# flip_flop_4LED.net
KiCad netlist of a schematic drawn in EAGLE
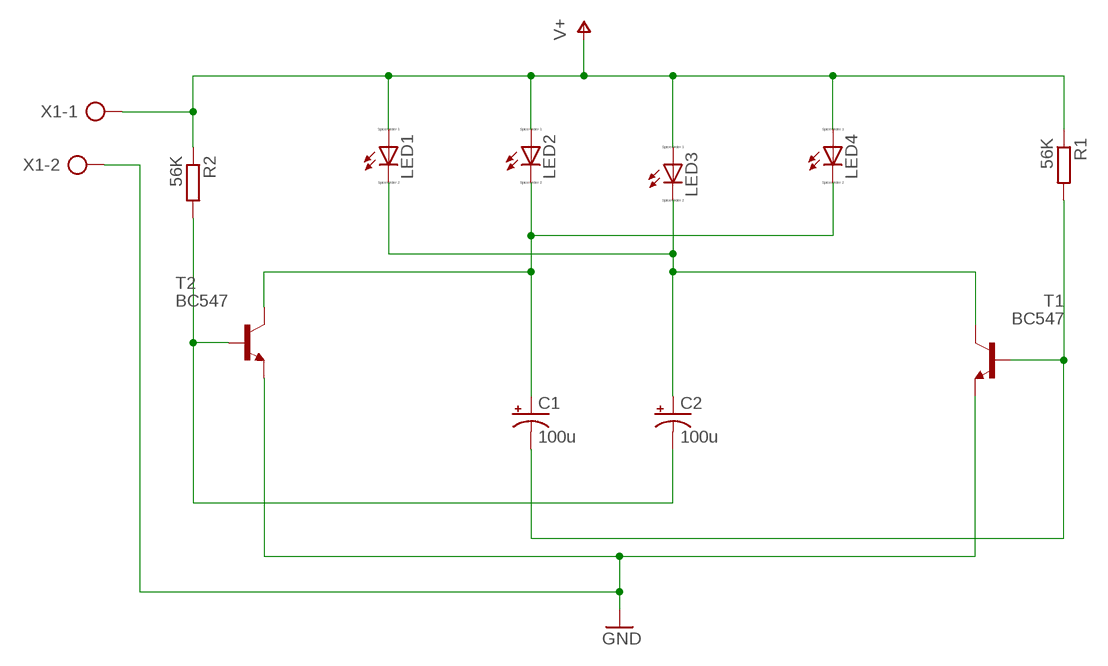
[diagram p0: schematic, sheet 1]

(export (version "E")
  (design (tool "Eeschema 10.0.6"))
  (components
    (comp (ref "C1")
      (value "100u")
      (footprint "eagle-import:E5-5")
      (libsource (lib "eagle-import") (part "CPOL-USE5-5"))
    )
    (comp (ref "C2")
      (value "100u")
      (footprint "eagle-import:E5-5")
      (libsource (lib "eagle-import") (part "CPOL-USE5-5"))
    )
    (comp (ref "LED1")
      (value "LED_ELD260")
      (footprint "eagle-import:LED_LD260")
      (libsource (lib "eagle-import") (part "LED_ELD260"))
    )
    (comp (ref "LED2")
      (value "LED_ELD260")
      (footprint "eagle-import:LED_LD260")
      (libsource (lib "eagle-import") (part "LED_ELD260"))
    )
    (comp (ref "LED3")
      (value "LED_ELD260")
      (footprint "eagle-import:LED_LD260")
      (libsource (lib "eagle-import") (part "LED_ELD260"))
    )
    (comp (ref "LED4")
      (value "LED_ELD260")
      (footprint "eagle-import:LED_LD260")
      (libsource (lib "eagle-import") (part "LED_ELD260"))
    )
    (comp (ref "R1")
      (value "56K")
      (footprint "eagle-import:0309_12")
      (libsource (lib "eagle-import") (part "R-EU_0309/12"))
    )
    (comp (ref "R2")
      (value "56K")
      (footprint "eagle-import:0309_12")
      (libsource (lib "eagle-import") (part "R-EU_0309/12"))
    )
    (comp (ref "T1")
      (value "BC547")
      (footprint "eagle-import:TO92")
      (libsource (lib "eagle-import") (part "BC547"))
    )
    (comp (ref "T2")
      (value "BC547")
      (footprint "eagle-import:TO92")
      (libsource (lib "eagle-import") (part "BC547"))
    )
    (comp (ref "X1")
      (value "AK500/2-H")
      (footprint "eagle-import:AK500_2-H")
      (libsource (lib "eagle-import") (part "AK500/2-H"))
    )
  )
  (nets
    (net (code "1") (name "GND") (class "Default")
      (node (ref "T1") (pin "1") (pinfunction "E_1") (pintype "passive"))
      (node (ref "T2") (pin "1") (pinfunction "E_1") (pintype "passive"))
      (node (ref "X1") (pin "2") (pinfunction "KL_2") (pintype "passive"))
    )
    (net (code "2") (name "Net-(LED1-C)") (class "Default")
      (node (ref "C2") (pin "+") (pinfunction "+_+") (pintype "passive"))
      (node (ref "LED1") (pin "K") (pinfunction "C_K") (pintype "passive"))
      (node (ref "LED3") (pin "K") (pinfunction "C_K") (pintype "passive"))
      (node (ref "T1") (pin "3") (pinfunction "C_3") (pintype "passive"))
    )
    (net (code "3") (name "Net-(LED2-C)") (class "Default")
      (node (ref "C1") (pin "+") (pinfunction "+_+") (pintype "passive"))
      (node (ref "LED2") (pin "K") (pinfunction "C_K") (pintype "passive"))
      (node (ref "LED4") (pin "K") (pinfunction "C_K") (pintype "passive"))
      (node (ref "T2") (pin "3") (pinfunction "C_3") (pintype "passive"))
    )
    (net (code "4") (name "Net-(T1-B)") (class "Default")
      (node (ref "C1") (pin "-") (pinfunction "-_-") (pintype "passive"))
      (node (ref "R1") (pin "2") (pinfunction "2_2") (pintype "passive"))
      (node (ref "T1") (pin "2") (pinfunction "B_2") (pintype "passive"))
    )
    (net (code "5") (name "Net-(T2-B)") (class "Default")
      (node (ref "C2") (pin "-") (pinfunction "-_-") (pintype "passive"))
      (node (ref "R2") (pin "2") (pinfunction "2_2") (pintype "passive"))
      (node (ref "T2") (pin "2") (pinfunction "B_2") (pintype "passive"))
    )
    (net (code "6") (name "V+") (class "Default")
      (node (ref "LED1") (pin "A") (pinfunction "A_A") (pintype "passive"))
      (node (ref "LED2") (pin "A") (pinfunction "A_A") (pintype "passive"))
      (node (ref "LED3") (pin "A") (pinfunction "A_A") (pintype "passive"))
      (node (ref "LED4") (pin "A") (pinfunction "A_A") (pintype "passive"))
      (node (ref "R1") (pin "1") (pinfunction "1_1") (pintype "passive"))
      (node (ref "R2") (pin "1") (pinfunction "1_1") (pintype "passive"))
      (node (ref "X1") (pin "1") (pinfunction "KL_1") (pintype "passive"))
    )
  )
)
